# pacman.net
KiCad netlist of a schematic drawn in EAGLE
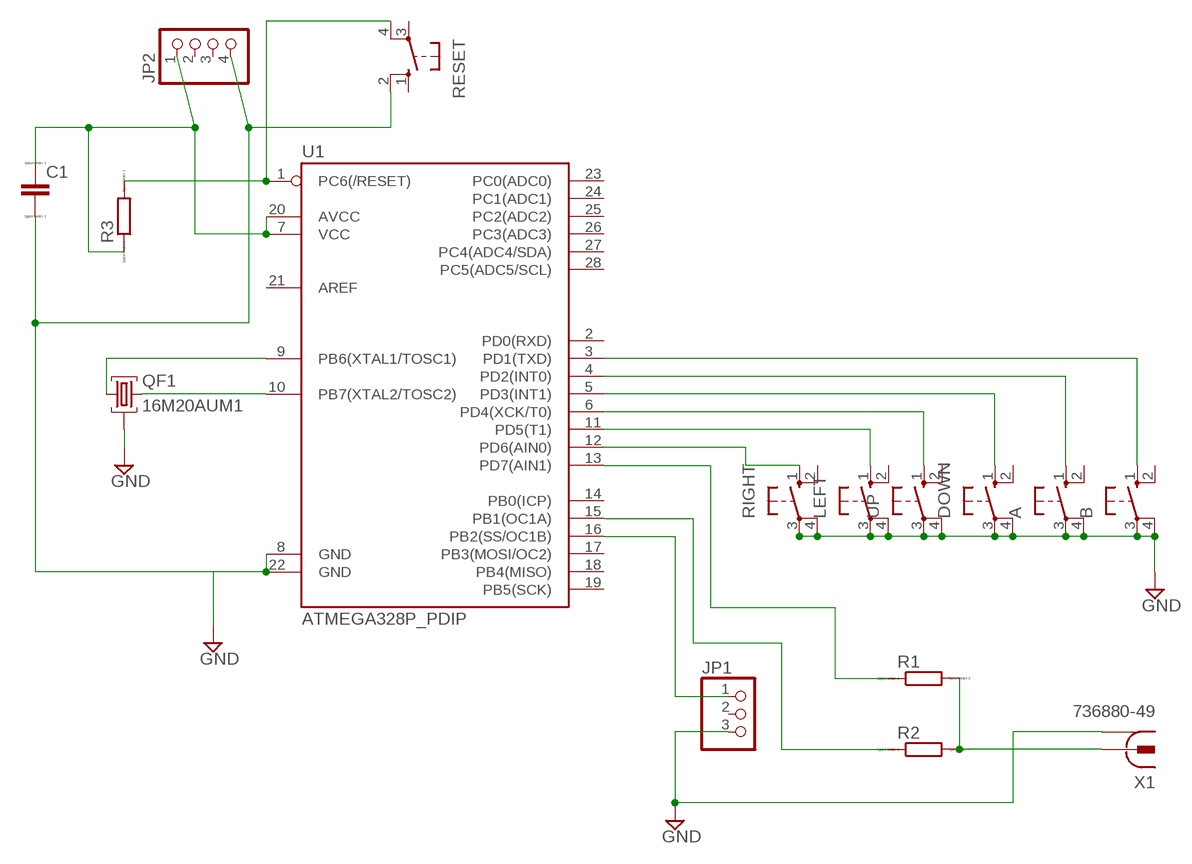
[diagram p0: schematic, sheet 1]

(export (version "E")
  (design (tool "Eeschema 10.0.6"))
  (components
    (comp (ref "A")
      (value "10-XX")
      (footprint "eagle-import:B3F-10XX")
      (fields (field (name "MPN") "B3F-1000"))
      (libsource (lib "eagle-import") (part "10-XX"))
    )
    (comp (ref "B")
      (value "10-XX")
      (footprint "eagle-import:B3F-10XX")
      (fields (field (name "MPN") "B3F-1000"))
      (libsource (lib "eagle-import") (part "10-XX"))
    )
    (comp (ref "C1")
      (value "CC3225")
      (footprint "eagle-import:C3225")
      (libsource (lib "eagle-import") (part "CC3225"))
    )
    (comp (ref "DOWN")
      (value "10-XX")
      (footprint "eagle-import:B3F-10XX")
      (fields (field (name "MPN") "B3F-1000"))
      (libsource (lib "eagle-import") (part "10-XX"))
    )
    (comp (ref "JP1")
      (value "PINHD-1X3")
      (footprint "eagle-import:1X03")
      (libsource (lib "eagle-import") (part "PINHD-1X3"))
    )
    (comp (ref "JP2")
      (value "PINHD-1X4")
      (footprint "eagle-import:1X04")
      (libsource (lib "eagle-import") (part "PINHD-1X4"))
    )
    (comp (ref "LEFT")
      (value "10-XX")
      (footprint "eagle-import:B3F-10XX")
      (fields (field (name "MPN") "B3F-1000"))
      (libsource (lib "eagle-import") (part "10-XX"))
    )
    (comp (ref "QF1")
      (value "16M20AUM1")
      (footprint "eagle-import:UM1")
      (libsource (lib "eagle-import") (part "16M20AUM1"))
    )
    (comp (ref "R1")
      (value "RR0603")
      (footprint "eagle-import:R0603")
      (libsource (lib "eagle-import") (part "RR0603"))
    )
    (comp (ref "R2")
      (value "RR0603")
      (footprint "eagle-import:R0603")
      (libsource (lib "eagle-import") (part "RR0603"))
    )
    (comp (ref "R3")
      (value "RR0603")
      (footprint "eagle-import:R0603")
      (libsource (lib "eagle-import") (part "RR0603"))
    )
    (comp (ref "RESET")
      (value "10-XX")
      (footprint "eagle-import:B3F-10XX")
      (fields (field (name "MPN") "B3F-1000"))
      (libsource (lib "eagle-import") (part "10-XX"))
    )
    (comp (ref "RIGHT")
      (value "10-XX")
      (footprint "eagle-import:B3F-10XX")
      (fields (field (name "MPN") "B3F-1000"))
      (libsource (lib "eagle-import") (part "10-XX"))
    )
    (comp (ref "U1")
      (value "ATMEGA328P_PDIP")
      (footprint "eagle-import:DIL28-3")
      (libsource (lib "eagle-import") (part "ATMEGA328P_PDIP"))
    )
    (comp (ref "UP")
      (value "10-XX")
      (footprint "eagle-import:B3F-10XX")
      (fields (field (name "MPN") "B3F-1000"))
      (libsource (lib "eagle-import") (part "10-XX"))
    )
    (comp (ref "X1")
      (value "736880-49")
      (footprint "eagle-import:736880-49")
      (libsource (lib "eagle-import") (part "736880-49"))
    )
  )
  (nets
    (net (code "1") (name "GND") (class "Default")
      (node (ref "A") (pin "3") (pinfunction "P_3") (pintype "passive"))
      (node (ref "A") (pin "4") (pinfunction "P1_4") (pintype "passive"))
      (node (ref "B") (pin "3") (pinfunction "P_3") (pintype "passive"))
      (node (ref "B") (pin "4") (pinfunction "P1_4") (pintype "passive"))
      (node (ref "C1") (pin "2") (pinfunction "2_2") (pintype "passive"))
      (node (ref "DOWN") (pin "3") (pinfunction "P_3") (pintype "passive"))
      (node (ref "DOWN") (pin "4") (pinfunction "P1_4") (pintype "passive"))
      (node (ref "JP1") (pin "3") (pinfunction "3_3") (pintype "passive"))
      (node (ref "JP2") (pin "4") (pinfunction "4_4") (pintype "passive"))
      (node (ref "LEFT") (pin "3") (pinfunction "P_3") (pintype "passive"))
      (node (ref "LEFT") (pin "4") (pinfunction "P1_4") (pintype "passive"))
      (node (ref "QF1") (pin "2") (pinfunction "2_2") (pintype "passive"))
      (node (ref "RESET") (pin "2") (pinfunction "S1_2") (pintype "passive"))
      (node (ref "RIGHT") (pin "3") (pinfunction "P_3") (pintype "passive"))
      (node (ref "RIGHT") (pin "4") (pinfunction "P1_4") (pintype "passive"))
      (node (ref "U1") (pin "22") (pinfunction "GND_22") (pintype "bidirectional"))
      (node (ref "U1") (pin "8") (pinfunction "GND_8") (pintype "bidirectional"))
      (node (ref "UP") (pin "3") (pinfunction "P_3") (pintype "passive"))
      (node (ref "UP") (pin "4") (pinfunction "P1_4") (pintype "passive"))
      (node (ref "X1") (pin "1") (pinfunction "1_1") (pintype "passive"))
      (node (ref "X1") (pin "1@1") (pinfunction "1_1@1") (pintype "passive"))
      (node (ref "X1") (pin "1@2") (pinfunction "1_1@2") (pintype "passive"))
    )
    (net (code "2") (name "Net-(A-S)") (class "Default")
      (node (ref "A") (pin "1") (pinfunction "S_1") (pintype "passive"))
      (node (ref "U1") (pin "4") (pinfunction "PD2(INT0)_4") (pintype "bidirectional"))
    )
    (net (code "3") (name "Net-(B-S)") (class "Default")
      (node (ref "B") (pin "1") (pinfunction "S_1") (pintype "passive"))
      (node (ref "U1") (pin "3") (pinfunction "PD1(TXD)_3") (pintype "bidirectional"))
    )
    (net (code "4") (name "Net-(DOWN-S)") (class "Default")
      (node (ref "DOWN") (pin "1") (pinfunction "S_1") (pintype "passive"))
      (node (ref "U1") (pin "5") (pinfunction "PD3(INT1)_5") (pintype "bidirectional"))
    )
    (net (code "5") (name "Net-(LEFT-S)") (class "Default")
      (node (ref "LEFT") (pin "1") (pinfunction "S_1") (pintype "passive"))
      (node (ref "U1") (pin "11") (pinfunction "PD5(T1)_11") (pintype "bidirectional"))
    )
    (net (code "6") (name "Net-(R1-Pad2)") (class "Default")
      (node (ref "R1") (pin "2") (pinfunction "2_2") (pintype "passive"))
      (node (ref "R2") (pin "2") (pinfunction "2_2") (pintype "passive"))
      (node (ref "X1") (pin "2") (pinfunction "2_2") (pintype "passive"))
    )
    (net (code "7") (name "Net-(RESET-P1)") (class "Default")
      (node (ref "R3") (pin "2") (pinfunction "2_2") (pintype "passive"))
      (node (ref "RESET") (pin "4") (pinfunction "P1_4") (pintype "passive"))
      (node (ref "U1") (pin "1") (pinfunction "PC6(/RESET)_1") (pintype "bidirectional"))
    )
    (net (code "8") (name "Net-(RIGHT-S)") (class "Default")
      (node (ref "RIGHT") (pin "1") (pinfunction "S_1") (pintype "passive"))
      (node (ref "U1") (pin "12") (pinfunction "PD6(AIN0)_12") (pintype "bidirectional"))
    )
    (net (code "9") (name "Net-(U1-AVCC)") (class "Default")
      (node (ref "C1") (pin "1") (pinfunction "1_1") (pintype "passive"))
      (node (ref "JP2") (pin "1") (pinfunction "1_1") (pintype "passive"))
      (node (ref "R3") (pin "1") (pinfunction "1_1") (pintype "passive"))
      (node (ref "U1") (pin "20") (pinfunction "AVCC_20") (pintype "bidirectional"))
      (node (ref "U1") (pin "7") (pinfunction "VCC_7") (pintype "bidirectional"))
    )
    (net (code "10") (name "Net-(U1-PB1(OC1A))") (class "Default")
      (node (ref "R2") (pin "1") (pinfunction "1_1") (pintype "passive"))
      (node (ref "U1") (pin "15") (pinfunction "PB1(OC1A)_15") (pintype "bidirectional"))
    )
    (net (code "11") (name "Net-(U1-PB2(SS{slash}OC1B))") (class "Default")
      (node (ref "JP1") (pin "1") (pinfunction "1_1") (pintype "passive"))
      (node (ref "U1") (pin "16") (pinfunction "PB2(SS/OC1B)_16") (pintype "bidirectional"))
    )
    (net (code "12") (name "Net-(U1-PB6(XTAL1{slash}TOSC1))") (class "Default")
      (node (ref "QF1") (pin "1") (pinfunction "1_1") (pintype "passive"))
      (node (ref "U1") (pin "9") (pinfunction "PB6(XTAL1/TOSC1)_9") (pintype "bidirectional"))
    )
    (net (code "13") (name "Net-(U1-PB7(XTAL2{slash}TOSC2))") (class "Default")
      (node (ref "QF1") (pin "3") (pinfunction "3_3") (pintype "passive"))
      (node (ref "U1") (pin "10") (pinfunction "PB7(XTAL2/TOSC2)_10") (pintype "bidirectional"))
    )
    (net (code "14") (name "Net-(U1-PD4(XCK{slash}T0))") (class "Default")
      (node (ref "U1") (pin "6") (pinfunction "PD4(XCK/T0)_6") (pintype "bidirectional"))
      (node (ref "UP") (pin "1") (pinfunction "S_1") (pintype "passive"))
    )
    (net (code "15") (name "Net-(U1-PD7(AIN1))") (class "Default")
      (node (ref "R1") (pin "1") (pinfunction "1_1") (pintype "passive"))
      (node (ref "U1") (pin "13") (pinfunction "PD7(AIN1)_13") (pintype "bidirectional"))
    )
    (net (code "16") (name "unconnected-(A-S1-Pad2)") (class "Default")
      (node (ref "A") (pin "2") (pinfunction "S1_2") (pintype "passive"))
    )
    (net (code "17") (name "unconnected-(B-S1-Pad2)") (class "Default")
      (node (ref "B") (pin "2") (pinfunction "S1_2") (pintype "passive"))
    )
    (net (code "18") (name "unconnected-(DOWN-S1-Pad2)") (class "Default")
      (node (ref "DOWN") (pin "2") (pinfunction "S1_2") (pintype "passive"))
    )
    (net (code "19") (name "unconnected-(JP1-Pad2)") (class "Default")
      (node (ref "JP1") (pin "2") (pinfunction "2_2") (pintype "passive"))
    )
    (net (code "20") (name "unconnected-(JP2-Pad2)") (class "Default")
      (node (ref "JP2") (pin "2") (pinfunction "2_2") (pintype "passive"))
    )
    (net (code "21") (name "unconnected-(JP2-Pad3)") (class "Default")
      (node (ref "JP2") (pin "3") (pinfunction "3_3") (pintype "passive"))
    )
    (net (code "22") (name "unconnected-(LEFT-S1-Pad2)") (class "Default")
      (node (ref "LEFT") (pin "2") (pinfunction "S1_2") (pintype "passive"))
    )
    (net (code "23") (name "unconnected-(RESET-P-Pad3)") (class "Default")
      (node (ref "RESET") (pin "3") (pinfunction "P_3") (pintype "passive"))
    )
    (net (code "24") (name "unconnected-(RESET-S-Pad1)") (class "Default")
      (node (ref "RESET") (pin "1") (pinfunction "S_1") (pintype "passive"))
    )
    (net (code "25") (name "unconnected-(RIGHT-S1-Pad2)") (class "Default")
      (node (ref "RIGHT") (pin "2") (pinfunction "S1_2") (pintype "passive"))
    )
    (net (code "26") (name "unconnected-(U1-AREF-Pad21)") (class "Default")
      (node (ref "U1") (pin "21") (pinfunction "AREF_21") (pintype "bidirectional"))
    )
    (net (code "27") (name "unconnected-(U1-PB0(ICP)-Pad14)") (class "Default")
      (node (ref "U1") (pin "14") (pinfunction "PB0(ICP)_14") (pintype "bidirectional"))
    )
    (net (code "28") (name "unconnected-(U1-PB3(MOSI{slash}OC2)-Pad17)") (class "Default")
      (node (ref "U1") (pin "17") (pinfunction "PB3(MOSI/OC2)_17") (pintype "bidirectional"))
    )
    (net (code "29") (name "unconnected-(U1-PB4(MISO)-Pad18)") (class "Default")
      (node (ref "U1") (pin "18") (pinfunction "PB4(MISO)_18") (pintype "bidirectional"))
    )
    (net (code "30") (name "unconnected-(U1-PB5(SCK)-Pad19)") (class "Default")
      (node (ref "U1") (pin "19") (pinfunction "PB5(SCK)_19") (pintype "bidirectional"))
    )
    (net (code "31") (name "unconnected-(U1-PC0(ADC0)-Pad23)") (class "Default")
      (node (ref "U1") (pin "23") (pinfunction "PC0(ADC0)_23") (pintype "bidirectional"))
    )
    (net (code "32") (name "unconnected-(U1-PC1(ADC1)-Pad24)") (class "Default")
      (node (ref "U1") (pin "24") (pinfunction "PC1(ADC1)_24") (pintype "bidirectional"))
    )
    (net (code "33") (name "unconnected-(U1-PC2(ADC2)-Pad25)") (class "Default")
      (node (ref "U1") (pin "25") (pinfunction "PC2(ADC2)_25") (pintype "bidirectional"))
    )
    (net (code "34") (name "unconnected-(U1-PC3(ADC3)-Pad26)") (class "Default")
      (node (ref "U1") (pin "26") (pinfunction "PC3(ADC3)_26") (pintype "bidirectional"))
    )
    (net (code "35") (name "unconnected-(U1-PC4(ADC4{slash}SDA)-Pad27)") (class "Default")
      (node (ref "U1") (pin "27") (pinfunction "PC4(ADC4/SDA)_27") (pintype "bidirectional"))
    )
    (net (code "36") (name "unconnected-(U1-PC5(ADC5{slash}SCL)-Pad28)") (class "Default")
      (node (ref "U1") (pin "28") (pinfunction "PC5(ADC5/SCL)_28") (pintype "bidirectional"))
    )
    (net (code "37") (name "unconnected-(U1-PD0(RXD)-Pad2)") (class "Default")
      (node (ref "U1") (pin "2") (pinfunction "PD0(RXD)_2") (pintype "bidirectional"))
    )
    (net (code "38") (name "unconnected-(UP-S1-Pad2)") (class "Default")
      (node (ref "UP") (pin "2") (pinfunction "S1_2") (pintype "passive"))
    )
  )
)
